# MB1297_STLINK_V2-1.net
KiCad netlist of a schematic drawn in Altium Designer
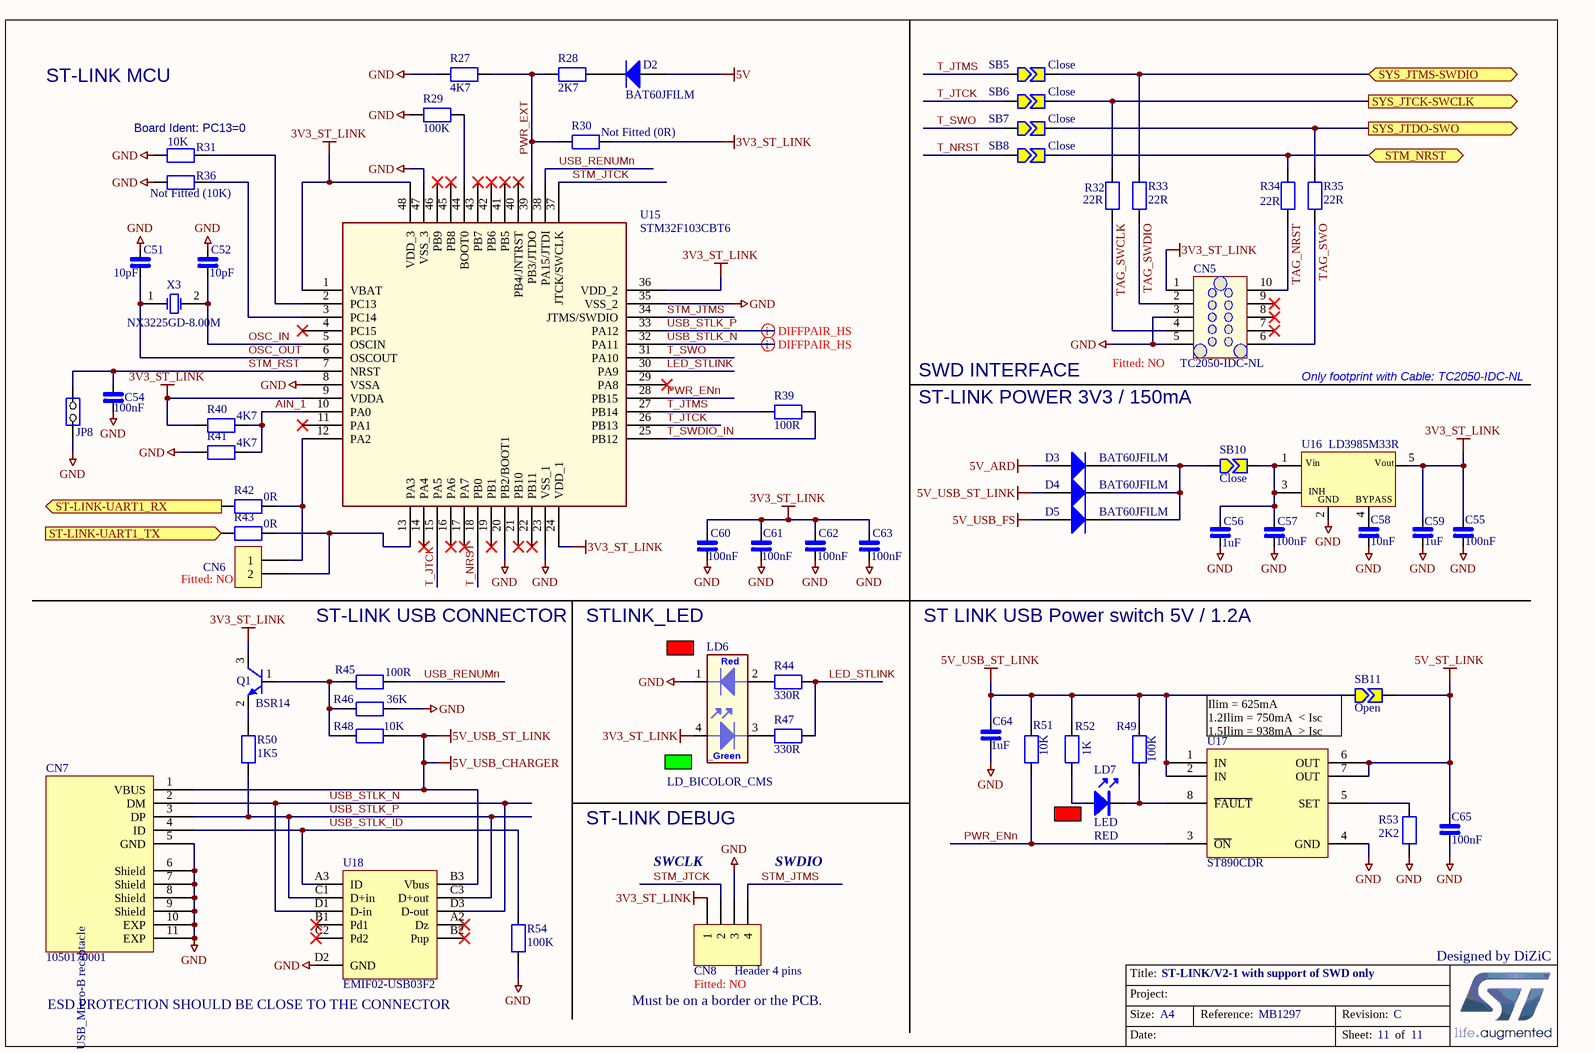
[diagram p0: MB1297_STLINK_V2-1.SCHDOC]

(export (version "E")
  (design (tool "Eeschema 10.0.6"))
  (components
    (comp (ref "C51")
      (value "10pF")
      (footprint "0402_CAP_NPOL")
      (description "Capacitor_not polarized")
      (libsource (lib "ST_Lib3D") (part "CAP_NPOL"))
    )
    (comp (ref "C52")
      (value "10pF")
      (footprint "0402_CAP_NPOL")
      (description "Capacitor_not polarized")
      (libsource (lib "ST_Lib3D") (part "CAP_NPOL"))
    )
    (comp (ref "C54")
      (value "100nF")
      (footprint "0402_CAP_NPOL")
      (description "Capacitor_not polarized")
      (libsource (lib "ST_Lib3D") (part "CAP_NPOL"))
    )
    (comp (ref "C55")
      (value "100nF")
      (footprint "0402_CAP_NPOL")
      (description "Capacitor_not polarized")
      (libsource (lib "ST_Lib3D") (part "CAP_NPOL"))
    )
    (comp (ref "C56")
      (value "1uF")
      (footprint "0402_CAP_NPOL")
      (description "Capacitor_not polarized")
      (libsource (lib "ST_Lib3D") (part "CAP_NPOL"))
    )
    (comp (ref "C57")
      (value "100nF")
      (footprint "0402_CAP_NPOL")
      (description "Capacitor_not polarized")
      (libsource (lib "ST_Lib3D") (part "CAP_NPOL"))
    )
    (comp (ref "C58")
      (value "10nF")
      (footprint "0402_CAP_NPOL")
      (description "Capacitor_not polarized")
      (libsource (lib "ST_Lib3D") (part "CAP_NPOL"))
    )
    (comp (ref "C59")
      (value "1uF")
      (footprint "0402_CAP_NPOL")
      (description "Capacitor_not polarized")
      (libsource (lib "ST_Lib3D") (part "CAP_NPOL"))
    )
    (comp (ref "C60")
      (value "100nF")
      (footprint "0402_CAP_NPOL")
      (description "Capacitor_not polarized")
      (libsource (lib "ST_Lib3D") (part "CAP_NPOL"))
    )
    (comp (ref "C61")
      (value "100nF")
      (footprint "0402_CAP_NPOL")
      (description "Capacitor_not polarized")
      (libsource (lib "ST_Lib3D") (part "CAP_NPOL"))
    )
    (comp (ref "C62")
      (value "100nF")
      (footprint "0402_CAP_NPOL")
      (description "Capacitor_not polarized")
      (libsource (lib "ST_Lib3D") (part "CAP_NPOL"))
    )
    (comp (ref "C63")
      (value "100nF")
      (footprint "0402_CAP_NPOL")
      (description "Capacitor_not polarized")
      (libsource (lib "ST_Lib3D") (part "CAP_NPOL"))
    )
    (comp (ref "C64")
      (value "1uF")
      (footprint "0402_CAP_NPOL")
      (description "Capacitor_not polarized")
      (libsource (lib "ST_Lib3D") (part "CAP_NPOL"))
    )
    (comp (ref "C65")
      (value "100nF")
      (footprint "0402_CAP_NPOL")
      (description "Capacitor_not polarized")
      (libsource (lib "ST_Lib3D") (part "CAP_NPOL"))
    )
    (comp (ref "CN5")
      (value "TC2050-IDC-NL")
      (footprint "CON_TAG-C_TC2050-IDC-NL")
      (description "Tag_Connector Header, 10-Pin, Dual row No legs")
      (fields (field (name "FITTED") "NO"))
      (libsource (lib "MCD_TEMP_PCH") (part "Tag-10-C"))
    )
    (comp (ref "CN6")
      (value "header 2 pins 2.54mm")
      (footprint "CON_SAMTEC_TSW-102-07-G-S")
      (description "Header 2 pins")
      (fields (field (name "FITTED") "NO"))
      (libsource (lib "MCD_TEMP_PCH") (part "Header 2 pins"))
    )
    (comp (ref "CN7")
      (value "1050170001")
      (footprint "CON_USBMICROB_MOLEX_105017-0001_H2P90")
      (description "USB-MICRO-B, 1050170001, SMT, MOLEX")
      (libsource (lib "MCD_TEMP_PCH") (part "1050170001"))
    )
    (comp (ref "CN8")
      (value "Header 4 pins")
      (footprint "CON_SAMTEC_TSW-104-07-G-S")
      (description "Header, 4-Pin")
      (fields (field (name "FITTED") "NO"))
      (libsource (lib "MCD_TEMP_PCH") (part "Header 4"))
    )
    (comp (ref "D2")
      (value "BAT60JFILM")
      (footprint "DIO_SOD323")
      (libsource (lib "MCD_TEMP_PCH") (part "BAT60JFILM"))
    )
    (comp (ref "D3")
      (value "BAT60JFILM")
      (footprint "DIO_SOD323")
      (libsource (lib "MCD_TEMP_PCH") (part "BAT60JFILM"))
    )
    (comp (ref "D4")
      (value "BAT60JFILM")
      (footprint "DIO_SOD323")
      (libsource (lib "MCD_TEMP_PCH") (part "BAT60JFILM"))
    )
    (comp (ref "D5")
      (value "BAT60JFILM")
      (footprint "DIO_SOD323")
      (libsource (lib "MCD_TEMP_PCH") (part "BAT60JFILM"))
    )
    (comp (ref "JP8")
      (value "Jumper_2.54mm")
      (footprint "CON_SAMTEC_TSW-102-07-G-S")
      (description "Connector jumper 1 position")
      (libsource (lib "MCD_TEMP_PCH") (part "TSW-102-07-x-S"))
    )
    (comp (ref "LD6")
      (value "LD_BICOLOR_CMS")
      (footprint "LED_BI-GR_HSMF-A201-A00J1")
      (description "Bicolor Led")
      (libsource (lib "MCD_TEMP_PCH") (part "LD_BICOLOR_CMS"))
    )
    (comp (ref "LD7")
      (value "LED")
      (footprint "0603_LED_RED")
      (description "Light-Emitting Diode")
      (fields (field (name "COLOR") "RED"))
      (libsource (lib "ST_Lib3D") (part "LED"))
    )
    (comp (ref "Q1")
      (value "BSR14")
      (footprint "ST_Lib3D:SOT23-3")
      (description "BSR14 NPN switching transistor SOT23 (Marking U8)")
      (libsource (lib "ST_Lib3D") (part "BSR14"))
    )
    (comp (ref "R27")
      (value "4K7")
      (footprint "0402_RES")
      (description "Resistor")
      (libsource (lib "Lib3D_Altium10_Schlib") (part "RES"))
    )
    (comp (ref "R28")
      (value "2K7")
      (footprint "0402_RES")
      (description "Resistor")
      (libsource (lib "Lib3D_Altium10_Schlib") (part "RES"))
    )
    (comp (ref "R29")
      (value "100K")
      (footprint "0402_RES")
      (description "Resistor")
      (libsource (lib "Lib3D_Altium10_Schlib") (part "RES"))
    )
    (comp (ref "R30")
      (value "Not Fitted (0R)")
      (footprint "0402_RES")
      (description "Resistor")
      (libsource (lib "Lib3D_Altium10_Schlib") (part "RES"))
    )
    (comp (ref "R31")
      (value "10K")
      (footprint "0402_RES")
      (description "Resistor")
      (libsource (lib "Lib3D_Altium10_Schlib") (part "RES"))
    )
    (comp (ref "R32")
      (value "22R")
      (footprint "0402_RES")
      (description "Resistor")
      (libsource (lib "Lib3D_Altium10_Schlib") (part "RES"))
    )
    (comp (ref "R33")
      (value "22R")
      (footprint "0402_RES")
      (description "Resistor")
      (libsource (lib "Lib3D_Altium10_Schlib") (part "RES"))
    )
    (comp (ref "R34")
      (value "22R")
      (footprint "0402_RES")
      (description "Resistor")
      (libsource (lib "Lib3D_Altium10_Schlib") (part "RES"))
    )
    (comp (ref "R35")
      (value "22R")
      (footprint "0402_RES")
      (description "Resistor")
      (libsource (lib "Lib3D_Altium10_Schlib") (part "RES"))
    )
    (comp (ref "R36")
      (value "Not Fitted (10K)")
      (footprint "0402_RES")
      (description "Resistor")
      (libsource (lib "Lib3D_Altium10_Schlib") (part "RES"))
    )
    (comp (ref "R39")
      (value "100R")
      (footprint "0402_RES")
      (description "Resistor")
      (libsource (lib "Lib3D_Altium10_Schlib") (part "RES"))
    )
    (comp (ref "R40")
      (value "4K7")
      (footprint "0402_RES")
      (description "Resistor")
      (libsource (lib "Lib3D_Altium10_Schlib") (part "RES"))
    )
    (comp (ref "R41")
      (value "4K7")
      (footprint "0402_RES")
      (description "Resistor")
      (libsource (lib "Lib3D_Altium10_Schlib") (part "RES"))
    )
    (comp (ref "R42")
      (value "0R")
      (footprint "0402_RES")
      (description "Resistor")
      (libsource (lib "Lib3D_Altium10_Schlib") (part "RES"))
    )
    (comp (ref "R43")
      (value "0R")
      (footprint "0402_RES")
      (description "Resistor")
      (libsource (lib "Lib3D_Altium10_Schlib") (part "RES"))
    )
    (comp (ref "R44")
      (value "330R")
      (footprint "0402_RES")
      (description "Resistor")
      (libsource (lib "Lib3D_Altium10_Schlib") (part "RES"))
    )
    (comp (ref "R45")
      (value "100R")
      (footprint "0402_RES")
      (description "Resistor")
      (libsource (lib "Lib3D_Altium10_Schlib") (part "RES"))
    )
    (comp (ref "R46")
      (value "36K")
      (footprint "0402_RES")
      (description "Resistor")
      (libsource (lib "Lib3D_Altium10_Schlib") (part "RES"))
    )
    (comp (ref "R47")
      (value "330R")
      (footprint "0402_RES")
      (description "Resistor")
      (libsource (lib "Lib3D_Altium10_Schlib") (part "RES"))
    )
    (comp (ref "R48")
      (value "10K")
      (footprint "0402_RES")
      (description "Resistor")
      (libsource (lib "Lib3D_Altium10_Schlib") (part "RES"))
    )
    (comp (ref "R49")
      (value "100K")
      (footprint "0402_RES")
      (description "Resistor")
      (libsource (lib "Lib3D_Altium10_Schlib") (part "RES"))
    )
    (comp (ref "R50")
      (value "1K5")
      (footprint "0402_RES")
      (description "Resistor")
      (libsource (lib "Lib3D_Altium10_Schlib") (part "RES"))
    )
    (comp (ref "R51")
      (value "10K")
      (footprint "0402_RES")
      (description "Resistor")
      (libsource (lib "Lib3D_Altium10_Schlib") (part "RES"))
    )
    (comp (ref "R52")
      (value "1K")
      (footprint "0402_RES")
      (description "Resistor")
      (libsource (lib "Lib3D_Altium10_Schlib") (part "RES"))
    )
    (comp (ref "R53")
      (value "2K2")
      (footprint "0402_RES")
      (description "Resistor")
      (libsource (lib "Lib3D_Altium10_Schlib") (part "RES"))
    )
    (comp (ref "R54")
      (value "100K")
      (footprint "0402_RES")
      (description "Resistor")
      (libsource (lib "Lib3D_Altium10_Schlib") (part "RES"))
    )
    (comp (ref "SB5")
      (value "Close")
      (footprint "SB")
      (description "Solder Jumper")
      (fields (field (name "PUBLISHER") "Altium Limited"))
      (libsource (lib "Lib3D_Altium10_Schlib") (part "Strap2"))
    )
    (comp (ref "SB6")
      (value "Close")
      (footprint "SB")
      (description "Solder Jumper")
      (fields (field (name "PUBLISHER") "Altium Limited"))
      (libsource (lib "Lib3D_Altium10_Schlib") (part "Strap2"))
    )
    (comp (ref "SB7")
      (value "Close")
      (footprint "SB")
      (description "Solder Jumper")
      (fields (field (name "PUBLISHER") "Altium Limited"))
      (libsource (lib "Lib3D_Altium10_Schlib") (part "Strap2"))
    )
    (comp (ref "SB8")
      (value "Close")
      (footprint "SB")
      (description "Solder Jumper")
      (fields (field (name "PUBLISHER") "Altium Limited"))
      (libsource (lib "Lib3D_Altium10_Schlib") (part "Strap2"))
    )
    (comp (ref "SB10")
      (value "Close")
      (footprint "SB")
      (description "Solder Jumper")
      (fields (field (name "PUBLISHER") "Altium Limited"))
      (libsource (lib "Lib3D_Altium10_Schlib") (part "Strap2"))
    )
    (comp (ref "SB11")
      (value "Open")
      (footprint "SB")
      (description "Solder Jumper")
      (fields (field (name "PUBLISHER") "Altium Limited"))
      (libsource (lib "Lib3D_Altium10_Schlib") (part "Strap2"))
    )
    (comp (ref "U15")
      (value "STM32F103CBT6")
      (footprint "ICC_LQFP48_7X7_P050")
      (description "Medium-density performance line ARM-based 32-bit MCU with 128KB Flash")
      (libsource (lib "MCD_TEMP_PCH") (part "STM32F103CBT6"))
    )
    (comp (ref "U16")
      (value "LD3985M33R")
      (footprint "REG_SOT23-5L")
      (description "Ultra low drop-low noise BiCMOS voltage, regulators low ESR capacitors compatible")
      (libsource (lib "MCD_TEMP_PCH") (part "LD3985M33R"))
    )
    (comp (ref "U17")
      (value "ST890CDR")
      (footprint "ICC_SO8_5X4_P127")
      (description "1.2 A current limited high-side power switch with thermal shutdown")
      (libsource (lib "MCD_TEMP_PCH") (part "ST890CDR"))
    )
    (comp (ref "U18")
      (value "EMIF02-USB03F2")
      (footprint "ESD_FLIP-CHIP-BGA11_1P44X1P94_P050")
      (description "2-line IPAD, EMI filter including ESD protection")
      (libsource (lib "MCD_TEMP_PCH") (part "EMIF02-USB03F2"))
    )
    (comp (ref "X3")
      (value "NX3225GD-8.00M")
      (footprint "CRY_NX3225GD_2P")
      (description "Crystal 8Mhz, 8pF, -+50PPM, SMD")
      (libsource (lib "MCD_TEMP_PCH") (part "XTAL_8M_NX3225GD"))
    )
  )
  (nets
    (net (code "1") (name "/AIN_1") (class "Default")
      (node (ref "R40") (pin "1") (pinfunction "1_1") (pintype "passive"))
      (node (ref "R41") (pin "1") (pinfunction "1_1") (pintype "passive"))
      (node (ref "U15") (pin "10") (pinfunction "PA0_10") (pintype "passive"))
    )
    (net (code "2") (name "/LED_STLINK") (class "Default")
      (node (ref "R44") (pin "1") (pinfunction "1_1") (pintype "passive"))
      (node (ref "R47") (pin "1") (pinfunction "1_1") (pintype "passive"))
      (node (ref "U15") (pin "30") (pinfunction "PA9_30") (pintype "passive"))
    )
    (net (code "3") (name "/OSC_IN") (class "Default")
      (node (ref "C52") (pin "2") (pinfunction "2_2") (pintype "passive"))
      (node (ref "U15") (pin "5") (pinfunction "OSCIN_5") (pintype "passive"))
      (node (ref "X3") (pin "2") (pinfunction "OSC2_2") (pintype "passive"))
    )
    (net (code "4") (name "/OSC_OUT") (class "Default")
      (node (ref "C51") (pin "2") (pinfunction "2_2") (pintype "passive"))
      (node (ref "U15") (pin "6") (pinfunction "OSCOUT_6") (pintype "passive"))
      (node (ref "X3") (pin "1") (pinfunction "OSC1_1") (pintype "passive"))
    )
    (net (code "5") (name "/PWR_ENn") (class "Default")
      (node (ref "R51") (pin "1") (pinfunction "1_1") (pintype "passive"))
      (node (ref "U15") (pin "28") (pinfunction "PB15_28") (pintype "passive"))
      (node (ref "U17") (pin "3") (pinfunction "~{ON}_3") (pintype "passive"))
    )
    (net (code "6") (name "/PWR_EXT") (class "Default")
      (node (ref "R27") (pin "1") (pinfunction "1_1") (pintype "passive"))
      (node (ref "R28") (pin "2") (pinfunction "2_2") (pintype "passive"))
      (node (ref "R30") (pin "2") (pinfunction "2_2") (pintype "passive"))
      (node (ref "U15") (pin "39") (pinfunction "PB3/JTDO_39") (pintype "passive"))
    )
    (net (code "7") (name "/ST-LINK-UART1_RX") (class "Default")
      (node (ref "R42") (pin "2") (pinfunction "2_2") (pintype "passive"))
    )
    (net (code "8") (name "/ST-LINK-UART1_TX") (class "Default")
      (node (ref "R43") (pin "2") (pinfunction "2_2") (pintype "passive"))
    )
    (net (code "9") (name "/STM_JTCK") (class "Default")
      (node (ref "CN8") (pin "2") (pinfunction "2_2") (pintype "passive"))
      (node (ref "U15") (pin "37") (pinfunction "JTCK/SWCLK_37") (pintype "passive"))
    )
    (net (code "10") (name "/STM_JTMS") (class "Default")
      (node (ref "CN8") (pin "4") (pinfunction "4_4") (pintype "passive"))
      (node (ref "U15") (pin "34") (pinfunction "JTMS/SWDIO_34") (pintype "passive"))
    )
    (net (code "11") (name "/STM_NRST") (class "Default")
      (node (ref "R34") (pin "2") (pinfunction "2_2") (pintype "passive"))
      (node (ref "SB8") (pin "1") (pinfunction "1_1") (pintype "passive"))
    )
    (net (code "12") (name "/STM_RST") (class "Default")
      (node (ref "C54") (pin "1") (pinfunction "1_1") (pintype "passive"))
      (node (ref "JP8") (pin "2") (pinfunction "NO_2") (pintype "passive"))
      (node (ref "U15") (pin "7") (pinfunction "NRST_7") (pintype "passive"))
    )
    (net (code "13") (name "/SYS_JTCK-SWCLK") (class "Default")
      (node (ref "R32") (pin "2") (pinfunction "2_2") (pintype "passive"))
      (node (ref "SB6") (pin "1") (pinfunction "1_1") (pintype "passive"))
    )
    (net (code "14") (name "/SYS_JTDO-SWO") (class "Default")
      (node (ref "R35") (pin "2") (pinfunction "2_2") (pintype "passive"))
      (node (ref "SB7") (pin "1") (pinfunction "1_1") (pintype "passive"))
    )
    (net (code "15") (name "/SYS_JTMS-SWDIO") (class "Default")
      (node (ref "R33") (pin "2") (pinfunction "2_2") (pintype "passive"))
      (node (ref "SB5") (pin "1") (pinfunction "1_1") (pintype "passive"))
    )
    (net (code "16") (name "/TAG_NRST") (class "Default")
      (node (ref "CN5") (pin "10") (pinfunction "10_10") (pintype "passive"))
      (node (ref "R34") (pin "1") (pinfunction "1_1") (pintype "passive"))
    )
    (net (code "17") (name "/TAG_SWCLK") (class "Default")
      (node (ref "CN5") (pin "4") (pinfunction "4_4") (pintype "passive"))
      (node (ref "R32") (pin "1") (pinfunction "1_1") (pintype "passive"))
    )
    (net (code "18") (name "/TAG_SWDIO") (class "Default")
      (node (ref "CN5") (pin "2") (pinfunction "2_2") (pintype "passive"))
      (node (ref "R33") (pin "1") (pinfunction "1_1") (pintype "passive"))
    )
    (net (code "19") (name "/TAG_SWO") (class "Default")
      (node (ref "CN5") (pin "6") (pinfunction "6_6") (pintype "passive"))
      (node (ref "R35") (pin "1") (pinfunction "1_1") (pintype "passive"))
    )
    (net (code "20") (name "/T_JTCK") (class "Default")
      (node (ref "SB6") (pin "2") (pinfunction "2_2") (pintype "passive"))
      (node (ref "U15") (pin "15") (pinfunction "PA5_15") (pintype "passive"))
      (node (ref "U15") (pin "26") (pinfunction "PB13_26") (pintype "passive"))
    )
    (net (code "21") (name "/T_JTMS") (class "Default")
      (node (ref "R39") (pin "2") (pinfunction "2_2") (pintype "passive"))
      (node (ref "SB5") (pin "2") (pinfunction "2_2") (pintype "passive"))
      (node (ref "U15") (pin "27") (pinfunction "PB14_27") (pintype "passive"))
    )
    (net (code "22") (name "/T_NRST") (class "Default")
      (node (ref "SB8") (pin "2") (pinfunction "2_2") (pintype "passive"))
      (node (ref "U15") (pin "18") (pinfunction "PB0_18") (pintype "passive"))
    )
    (net (code "23") (name "/T_SWDIO_IN") (class "Default")
      (node (ref "R39") (pin "1") (pinfunction "1_1") (pintype "passive"))
      (node (ref "U15") (pin "25") (pinfunction "PB12_25") (pintype "passive"))
    )
    (net (code "24") (name "/T_SWO") (class "Default")
      (node (ref "SB7") (pin "2") (pinfunction "2_2") (pintype "passive"))
      (node (ref "U15") (pin "31") (pinfunction "PA10_31") (pintype "passive"))
    )
    (net (code "25") (name "/USB_RENUMn") (class "Default")
      (node (ref "R45") (pin "1") (pinfunction "1_1") (pintype "passive"))
      (node (ref "U15") (pin "38") (pinfunction "PA15/JTDI_38") (pintype "passive"))
    )
    (net (code "26") (name "/USB_STLK_ID") (class "Default")
      (node (ref "CN7") (pin "4") (pinfunction "ID_4") (pintype "passive"))
      (node (ref "R54") (pin "1") (pinfunction "1_1") (pintype "passive"))
      (node (ref "U18") (pin "A3") (pinfunction "ID_A3") (pintype "passive"))
    )
    (net (code "27") (name "/USB_STLK_N") (class "Default")
      (node (ref "CN7") (pin "2") (pinfunction "DM_2") (pintype "passive"))
      (node (ref "U15") (pin "32") (pinfunction "PA11_32") (pintype "passive"))
      (node (ref "U18") (pin "D1") (pinfunction "D-in_D1") (pintype "passive"))
      (node (ref "U18") (pin "D3") (pinfunction "D-out_D3") (pintype "passive"))
    )
    (net (code "28") (name "/USB_STLK_P") (class "Default")
      (node (ref "CN7") (pin "3") (pinfunction "DP_3") (pintype "passive"))
      (node (ref "R50") (pin "2") (pinfunction "2_2") (pintype "passive"))
      (node (ref "U15") (pin "33") (pinfunction "PA12_33") (pintype "passive"))
      (node (ref "U18") (pin "C1") (pinfunction "D+in_C1") (pintype "passive"))
      (node (ref "U18") (pin "C3") (pinfunction "D+out_C3") (pintype "passive"))
    )
    (net (code "29") (name "3V3_ST_LINK") (class "Default")
      (node (ref "C55") (pin "1") (pinfunction "1_1") (pintype "passive"))
      (node (ref "C59") (pin "1") (pinfunction "1_1") (pintype "passive"))
      (node (ref "C60") (pin "1") (pinfunction "1_1") (pintype "passive"))
      (node (ref "C61") (pin "1") (pinfunction "1_1") (pintype "passive"))
      (node (ref "C62") (pin "1") (pinfunction "1_1") (pintype "passive"))
      (node (ref "C63") (pin "1") (pinfunction "1_1") (pintype "passive"))
      (node (ref "CN5") (pin "1") (pinfunction "1_1") (pintype "passive"))
      (node (ref "CN8") (pin "1") (pinfunction "1_1") (pintype "passive"))
      (node (ref "LD6") (pin "4") (pinfunction "4_4") (pintype "passive"))
      (node (ref "Q1") (pin "3") (pinfunction "C_3") (pintype "passive"))
      (node (ref "R30") (pin "1") (pinfunction "1_1") (pintype "passive"))
      (node (ref "R40") (pin "2") (pinfunction "2_2") (pintype "passive"))
      (node (ref "U15") (pin "1") (pinfunction "VBAT_1") (pintype "passive"))
      (node (ref "U15") (pin "24") (pinfunction "VDD_1_24") (pintype "passive"))
      (node (ref "U15") (pin "36") (pinfunction "VDD_2_36") (pintype "passive"))
      (node (ref "U15") (pin "48") (pinfunction "VDD_3_48") (pintype "passive"))
      (node (ref "U15") (pin "9") (pinfunction "VDDA_9") (pintype "passive"))
      (node (ref "U16") (pin "5") (pinfunction "Vout_5") (pintype "passive"))
    )
    (net (code "30") (name "5V") (class "Default")
      (node (ref "D2") (pin "1") (pinfunction "A_1") (pintype "passive"))
    )
    (net (code "31") (name "5V_ARD") (class "Default")
      (node (ref "D3") (pin "1") (pinfunction "A_1") (pintype "passive"))
    )
    (net (code "32") (name "5V_ST_LINK") (class "Default")
      (node (ref "C65") (pin "1") (pinfunction "1_1") (pintype "passive"))
      (node (ref "SB11") (pin "1") (pinfunction "1_1") (pintype "passive"))
      (node (ref "U17") (pin "6") (pinfunction "OUT_6") (pintype "passive"))
      (node (ref "U17") (pin "7") (pinfunction "OUT_7") (pintype "passive"))
    )
    (net (code "33") (name "5V_USB_CHARGER") (class "Default")
      (node (ref "C64") (pin "1") (pinfunction "1_1") (pintype "passive"))
      (node (ref "CN7") (pin "1") (pinfunction "VBUS_1") (pintype "passive"))
      (node (ref "D4") (pin "1") (pinfunction "A_1") (pintype "passive"))
      (node (ref "R48") (pin "1") (pinfunction "1_1") (pintype "passive"))
      (node (ref "R49") (pin "2") (pinfunction "2_2") (pintype "passive"))
      (node (ref "R51") (pin "2") (pinfunction "2_2") (pintype "passive"))
      (node (ref "R52") (pin "2") (pinfunction "2_2") (pintype "passive"))
      (node (ref "SB11") (pin "2") (pinfunction "2_2") (pintype "passive"))
      (node (ref "U17") (pin "1") (pinfunction "IN_1") (pintype "passive"))
      (node (ref "U17") (pin "2") (pinfunction "IN_2") (pintype "passive"))
      (node (ref "U18") (pin "B3") (pinfunction "Vbus_B3") (pintype "passive"))
    )
    (net (code "34") (name "5V_USB_FS") (class "Default")
      (node (ref "D5") (pin "1") (pinfunction "A_1") (pintype "passive"))
    )
    (net (code "35") (name "GND") (class "Default")
      (node (ref "C51") (pin "1") (pinfunction "1_1") (pintype "passive"))
      (node (ref "C52") (pin "1") (pinfunction "1_1") (pintype "passive"))
      (node (ref "C54") (pin "2") (pinfunction "2_2") (pintype "passive"))
      (node (ref "C55") (pin "2") (pinfunction "2_2") (pintype "passive"))
      (node (ref "C56") (pin "2") (pinfunction "2_2") (pintype "passive"))
      (node (ref "C57") (pin "2") (pinfunction "2_2") (pintype "passive"))
      (node (ref "C58") (pin "2") (pinfunction "2_2") (pintype "passive"))
      (node (ref "C59") (pin "2") (pinfunction "2_2") (pintype "passive"))
      (node (ref "C60") (pin "2") (pinfunction "2_2") (pintype "passive"))
      (node (ref "C61") (pin "2") (pinfunction "2_2") (pintype "passive"))
      (node (ref "C62") (pin "2") (pinfunction "2_2") (pintype "passive"))
      (node (ref "C63") (pin "2") (pinfunction "2_2") (pintype "passive"))
      (node (ref "C64") (pin "2") (pinfunction "2_2") (pintype "passive"))
      (node (ref "C65") (pin "2") (pinfunction "2_2") (pintype "passive"))
      (node (ref "CN5") (pin "3") (pinfunction "3_3") (pintype "passive"))
      (node (ref "CN5") (pin "5") (pinfunction "5_5") (pintype "passive"))
      (node (ref "CN7") (pin "10") (pinfunction "EXP_10") (pintype "passive"))
      (node (ref "CN7") (pin "11") (pinfunction "EXP_11") (pintype "passive"))
      (node (ref "CN7") (pin "5") (pinfunction "GND_5") (pintype "passive"))
      (node (ref "CN7") (pin "6") (pinfunction "Shield_6") (pintype "passive"))
      (node (ref "CN7") (pin "7") (pinfunction "Shield_7") (pintype "passive"))
      (node (ref "CN7") (pin "8") (pinfunction "Shield_8") (pintype "passive"))
      (node (ref "CN7") (pin "9") (pinfunction "Shield_9") (pintype "passive"))
      (node (ref "CN8") (pin "3") (pinfunction "3_3") (pintype "passive"))
      (node (ref "JP8") (pin "1") (pinfunction "COMMON_1") (pintype "passive"))
      (node (ref "LD6") (pin "1") (pinfunction "1_1") (pintype "passive"))
      (node (ref "R27") (pin "2") (pinfunction "2_2") (pintype "passive"))
      (node (ref "R29") (pin "2") (pinfunction "2_2") (pintype "passive"))
      (node (ref "R31") (pin "2") (pinfunction "2_2") (pintype "passive"))
      (node (ref "R36") (pin "2") (pinfunction "2_2") (pintype "passive"))
      (node (ref "R41") (pin "2") (pinfunction "2_2") (pintype "passive"))
      (node (ref "R46") (pin "1") (pinfunction "1_1") (pintype "passive"))
      (node (ref "R53") (pin "1") (pinfunction "1_1") (pintype "passive"))
      (node (ref "R54") (pin "2") (pinfunction "2_2") (pintype "passive"))
      (node (ref "U15") (pin "20") (pinfunction "PB2/BOOT1_20") (pintype "passive"))
      (node (ref "U15") (pin "23") (pinfunction "VSS_1_23") (pintype "passive"))
      (node (ref "U15") (pin "35") (pinfunction "VSS_2_35") (pintype "passive"))
      (node (ref "U15") (pin "47") (pinfunction "VSS_3_47") (pintype "passive"))
      (node (ref "U15") (pin "8") (pinfunction "VSSA_8") (pintype "passive"))
      (node (ref "U16") (pin "2") (pinfunction "GND_2") (pintype "passive"))
      (node (ref "U17") (pin "4") (pinfunction "GND_4") (pintype "passive"))
      (node (ref "U18") (pin "D2") (pinfunction "GND_D2") (pintype "passive"))
    )
    (net (code "36") (name "Net-(D2-K)") (class "Default")
      (node (ref "D2") (pin "2") (pinfunction "K_2") (pintype "passive"))
      (node (ref "R28") (pin "1") (pinfunction "1_1") (pintype "passive"))
    )
    (net (code "37") (name "Net-(D3-K)") (class "Default")
      (node (ref "D3") (pin "2") (pinfunction "K_2") (pintype "passive"))
      (node (ref "D4") (pin "2") (pinfunction "K_2") (pintype "passive"))
      (node (ref "D5") (pin "2") (pinfunction "K_2") (pintype "passive"))
      (node (ref "SB10") (pin "2") (pinfunction "2_2") (pintype "passive"))
    )
    (net (code "38") (name "Net-(LD6-Pad2)") (class "Default")
      (node (ref "LD6") (pin "2") (pinfunction "2_2") (pintype "passive"))
      (node (ref "R44") (pin "2") (pinfunction "2_2") (pintype "passive"))
    )
    (net (code "39") (name "Net-(LD6-Pad3)") (class "Default")
      (node (ref "LD6") (pin "3") (pinfunction "3_3") (pintype "passive"))
      (node (ref "R47") (pin "2") (pinfunction "2_2") (pintype "passive"))
    )
    (net (code "40") (name "Net-(LD7-PadA)") (class "Default")
      (node (ref "LD7") (pin "A") (pinfunction "A_A") (pintype "passive"))
      (node (ref "R52") (pin "1") (pinfunction "1_1") (pintype "passive"))
    )
    (net (code "41") (name "Net-(Q1-B)") (class "Default")
      (node (ref "Q1") (pin "1") (pinfunction "B_1") (pintype "passive"))
      (node (ref "R45") (pin "2") (pinfunction "2_2") (pintype "passive"))
      (node (ref "R46") (pin "2") (pinfunction "2_2") (pintype "passive"))
      (node (ref "R48") (pin "2") (pinfunction "2_2") (pintype "passive"))
    )
    (net (code "42") (name "Net-(Q1-E)") (class "Default")
      (node (ref "Q1") (pin "2") (pinfunction "E_2") (pintype "passive"))
      (node (ref "R50") (pin "1") (pinfunction "1_1") (pintype "passive"))
    )
    (net (code "43") (name "Net-(U15-BOOT0)") (class "Default")
      (node (ref "R29") (pin "1") (pinfunction "1_1") (pintype "passive"))
      (node (ref "U15") (pin "44") (pinfunction "BOOT0_44") (pintype "passive"))
    )
    (net (code "44") (name "Net-(U15-PA2)") (class "Default")
      (node (ref "CN6") (pin "1") (pinfunction "1_1") (pintype "passive"))
      (node (ref "R42") (pin "1") (pinfunction "1_1") (pintype "passive"))
      (node (ref "U15") (pin "12") (pinfunction "PA2_12") (pintype "passive"))
    )
    (net (code "45") (name "Net-(U15-PA3)") (class "Default")
      (node (ref "CN6") (pin "2") (pinfunction "2_2") (pintype "passive"))
      (node (ref "R43") (pin "1") (pinfunction "1_1") (pintype "passive"))
      (node (ref "U15") (pin "13") (pinfunction "PA3_13") (pintype "passive"))
    )
    (net (code "46") (name "Net-(U15-PC13)") (class "Default")
      (node (ref "R31") (pin "1") (pinfunction "1_1") (pintype "passive"))
      (node (ref "U15") (pin "2") (pinfunction "PC13_2") (pintype "passive"))
    )
    (net (code "47") (name "Net-(U15-PC14)") (class "Default")
      (node (ref "R36") (pin "1") (pinfunction "1_1") (pintype "passive"))
      (node (ref "U15") (pin "3") (pinfunction "PC14_3") (pintype "passive"))
    )
    (net (code "48") (name "Net-(U16-BYPASS)") (class "Default")
      (node (ref "C58") (pin "1") (pinfunction "1_1") (pintype "passive"))
      (node (ref "U16") (pin "4") (pinfunction "BYPASS_4") (pintype "passive"))
    )
    (net (code "49") (name "Net-(U16-CE)") (class "Default")
      (node (ref "C56") (pin "1") (pinfunction "1_1") (pintype "passive"))
      (node (ref "C57") (pin "1") (pinfunction "1_1") (pintype "passive"))
      (node (ref "SB10") (pin "1") (pinfunction "1_1") (pintype "passive"))
      (node (ref "U16") (pin "1") (pinfunction "Vin_1") (pintype "passive"))
      (node (ref "U16") (pin "3") (pinfunction "CE_3") (pintype "passive"))
    )
    (net (code "50") (name "Net-(U17-SET)") (class "Default")
      (node (ref "R53") (pin "2") (pinfunction "2_2") (pintype "passive"))
      (node (ref "U17") (pin "5") (pinfunction "SET_5") (pintype "passive"))
    )
    (net (code "51") (name "Net-(U17-~{FAULT})") (class "Default")
      (node (ref "LD7") (pin "K") (pinfunction "K_K") (pintype "passive"))
      (node (ref "R49") (pin "1") (pinfunction "1_1") (pintype "passive"))
      (node (ref "U17") (pin "8") (pinfunction "~{FAULT}_8") (pintype "passive"))
    )
    (net (code "52") (name "unconnected-(CN5-Pad7)") (class "Default")
      (node (ref "CN5") (pin "7") (pinfunction "7_7") (pintype "passive+no_connect"))
    )
    (net (code "53") (name "unconnected-(CN5-Pad8)") (class "Default")
      (node (ref "CN5") (pin "8") (pinfunction "8_8") (pintype "passive+no_connect"))
    )
    (net (code "54") (name "unconnected-(CN5-Pad9)") (class "Default")
      (node (ref "CN5") (pin "9") (pinfunction "9_9") (pintype "passive+no_connect"))
    )
    (net (code "55") (name "unconnected-(U15-PA1-Pad11)") (class "Default")
      (node (ref "U15") (pin "11") (pinfunction "PA1_11") (pintype "passive+no_connect"))
    )
    (net (code "56") (name "unconnected-(U15-PA4-Pad14)") (class "Default")
      (node (ref "U15") (pin "14") (pinfunction "PA4_14") (pintype "passive+no_connect"))
    )
    (net (code "57") (name "unconnected-(U15-PA6-Pad16)") (class "Default")
      (node (ref "U15") (pin "16") (pinfunction "PA6_16") (pintype "passive+no_connect"))
    )
    (net (code "58") (name "unconnected-(U15-PA7-Pad17)") (class "Default")
      (node (ref "U15") (pin "17") (pinfunction "PA7_17") (pintype "passive+no_connect"))
    )
    (net (code "59") (name "unconnected-(U15-PA8-Pad29)") (class "Default")
      (node (ref "U15") (pin "29") (pinfunction "PA8_29") (pintype "passive+no_connect"))
    )
    (net (code "60") (name "unconnected-(U15-PB1-Pad19)") (class "Default")
      (node (ref "U15") (pin "19") (pinfunction "PB1_19") (pintype "passive+no_connect"))
    )
    (net (code "61") (name "unconnected-(U15-PB4{slash}JNTRST-Pad40)") (class "Default")
      (node (ref "U15") (pin "40") (pinfunction "PB4/JNTRST_40") (pintype "passive+no_connect"))
    )
    (net (code "62") (name "unconnected-(U15-PB5-Pad41)") (class "Default")
      (node (ref "U15") (pin "41") (pinfunction "PB5_41") (pintype "passive+no_connect"))
    )
    (net (code "63") (name "unconnected-(U15-PB6-Pad42)") (class "Default")
      (node (ref "U15") (pin "42") (pinfunction "PB6_42") (pintype "passive+no_connect"))
    )
    (net (code "64") (name "unconnected-(U15-PB7-Pad43)") (class "Default")
      (node (ref "U15") (pin "43") (pinfunction "PB7_43") (pintype "passive+no_connect"))
    )
    (net (code "65") (name "unconnected-(U15-PB8-Pad45)") (class "Default")
      (node (ref "U15") (pin "45") (pinfunction "PB8_45") (pintype "passive+no_connect"))
    )
    (net (code "66") (name "unconnected-(U15-PB9-Pad46)") (class "Default")
      (node (ref "U15") (pin "46") (pinfunction "PB9_46") (pintype "passive+no_connect"))
    )
    (net (code "67") (name "unconnected-(U15-PB10-Pad21)") (class "Default")
      (node (ref "U15") (pin "21") (pinfunction "PB10_21") (pintype "passive+no_connect"))
    )
    (net (code "68") (name "unconnected-(U15-PB11-Pad22)") (class "Default")
      (node (ref "U15") (pin "22") (pinfunction "PB11_22") (pintype "passive+no_connect"))
    )
    (net (code "69") (name "unconnected-(U15-PC15-Pad4)") (class "Default")
      (node (ref "U15") (pin "4") (pinfunction "PC15_4") (pintype "passive+no_connect"))
    )
    (net (code "70") (name "unconnected-(U18-Dz-PadA2)") (class "Default")
      (node (ref "U18") (pin "A2") (pinfunction "Dz_A2") (pintype "passive+no_connect"))
    )
    (net (code "71") (name "unconnected-(U18-Pd1-PadB1)") (class "Default")
      (node (ref "U18") (pin "B1") (pinfunction "Pd1_B1") (pintype "passive+no_connect"))
    )
    (net (code "72") (name "unconnected-(U18-Pd2-PadC2)") (class "Default")
      (node (ref "U18") (pin "C2") (pinfunction "Pd2_C2") (pintype "passive+no_connect"))
    )
    (net (code "73") (name "unconnected-(U18-Pup-PadB2)") (class "Default")
      (node (ref "U18") (pin "B2") (pinfunction "Pup_B2") (pintype "passive+no_connect"))
    )
  )
)
